# My_STM32_BOARD_MCU_SCH.net
KiCad netlist of a schematic drawn in Altium Designer
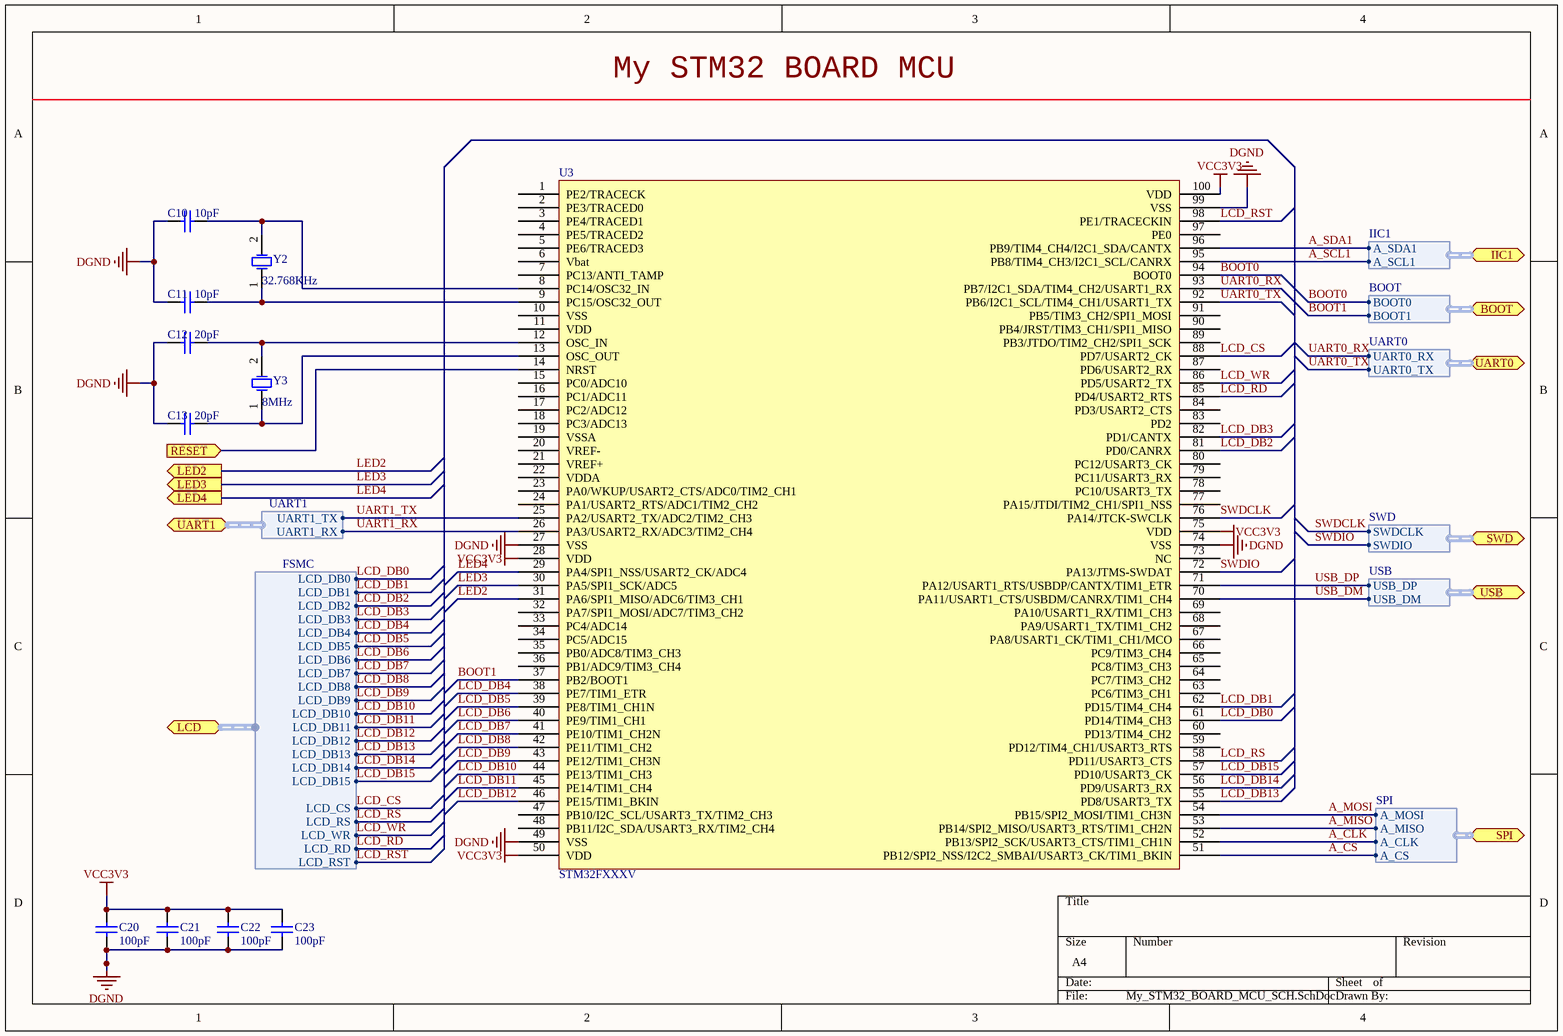
[diagram p0: My_STM32_BOARD_MCU_SCH.SchDoc]

(export (version "E")
  (design (tool "Eeschema 10.0.6"))
  (components
    (comp (ref "C10")
      (value "10pF")
      (footprint "0402")
      (description "Capacitor (Semiconductor SIM Model)")
      (fields (field (name "Comment") "Cap Semi") (field (name "PUBLISHER") "Altium Limited"))
      (libsource (lib "Miscellaneous Devices") (part "Cap Semi"))
    )
    (comp (ref "C11")
      (value "10pF")
      (footprint "0402")
      (description "Capacitor (Semiconductor SIM Model)")
      (fields (field (name "Comment") "Cap Semi") (field (name "PUBLISHER") "Altium Limited"))
      (libsource (lib "Miscellaneous Devices") (part "Cap Semi"))
    )
    (comp (ref "C12")
      (value "20pF")
      (footprint "0402")
      (description "Capacitor (Semiconductor SIM Model)")
      (fields (field (name "Comment") "Cap Semi") (field (name "PUBLISHER") "Altium Limited"))
      (libsource (lib "Miscellaneous Devices") (part "Cap Semi"))
    )
    (comp (ref "C13")
      (value "20pF")
      (footprint "0402")
      (description "Capacitor (Semiconductor SIM Model)")
      (fields (field (name "Comment") "Cap Semi") (field (name "PUBLISHER") "Altium Limited"))
      (libsource (lib "Miscellaneous Devices") (part "Cap Semi"))
    )
    (comp (ref "C20")
      (value "100pF")
      (footprint "0402")
      (description "Capacitor")
      (fields (field (name "Comment") "Cap") (field (name "PUBLISHER") "Altium Limited"))
      (libsource (lib "Miscellaneous Devices") (part "Cap"))
    )
    (comp (ref "C21")
      (value "100pF")
      (footprint "0402")
      (description "Capacitor")
      (fields (field (name "Comment") "Cap") (field (name "PUBLISHER") "Altium Limited"))
      (libsource (lib "Miscellaneous Devices") (part "Cap"))
    )
    (comp (ref "C22")
      (value "100pF")
      (footprint "0402")
      (description "Capacitor")
      (fields (field (name "Comment") "Cap") (field (name "PUBLISHER") "Altium Limited"))
      (libsource (lib "Miscellaneous Devices") (part "Cap"))
    )
    (comp (ref "C23")
      (value "100pF")
      (footprint "0402")
      (description "Capacitor")
      (fields (field (name "Comment") "Cap") (field (name "PUBLISHER") "Altium Limited"))
      (libsource (lib "Miscellaneous Devices") (part "Cap"))
    )
    (comp (ref "U3")
      (value "STM32FXXXV")
      (footprint "LQFP-100")
      (libsource (lib "My_Integrated_Library") (part "STM32FXXXV"))
    )
    (comp (ref "Y2")
      (value "32.768KHz")
      (footprint "XT_XTAL_32K")
      (description "XTAL")
      (libsource (lib "My_Integrated_Library") (part "XTAL"))
    )
    (comp (ref "Y3")
      (value "8MHz")
      (footprint "XT_HC49S_D")
      (description "XTAL")
      (libsource (lib "My_Integrated_Library") (part "XTAL"))
    )
  )
  (nets
    (net (code "9") (name "/A_CLK") (class "Default")
      (node (ref "U3") (pin "52") (pinfunction "PB13/SPI2_SCK/USART3_CTS/TIM1_CH1N_52") (pintype "passive"))
    )
    (net (code "10") (name "/A_CS") (class "Default")
      (node (ref "U3") (pin "51") (pinfunction "PB12/SPI2_NSS/I2C2_SMBAI/USART3_CK/TIM1_BKIN_51") (pintype "passive"))
    )
    (net (code "11") (name "/A_MISO") (class "Default")
      (node (ref "U3") (pin "53") (pinfunction "PB14/SPI2_MISO/USART3_RTS/TIM1_CH2N_53") (pintype "passive"))
    )
    (net (code "12") (name "/A_MOSI") (class "Default")
      (node (ref "U3") (pin "54") (pinfunction "PB15/SPI2_MOSI/TIM1_CH3N_54") (pintype "passive"))
    )
    (net (code "13") (name "/A_SCL1") (class "Default")
      (node (ref "U3") (pin "95") (pinfunction "PB8/TIM4_CH3/I2C1_SCL/CANRX_95") (pintype "passive"))
    )
    (net (code "14") (name "/A_SDA1") (class "Default")
      (node (ref "U3") (pin "96") (pinfunction "PB9/TIM4_CH4/I2C1_SDA/CANTX_96") (pintype "passive"))
    )
    (net (code "15") (name "/BOOT0") (class "Default")
      (node (ref "U3") (pin "94") (pinfunction "BOOT0_94") (pintype "passive"))
    )
    (net (code "16") (name "/BOOT1") (class "Default")
      (node (ref "U3") (pin "37") (pinfunction "PB2/BOOT1_37") (pintype "passive"))
    )
    (net (code "17") (name "/LCD_CS") (class "Default")
      (node (ref "U3") (pin "88") (pinfunction "PD7/USART2_CK_88") (pintype "passive"))
    )
    (net (code "18") (name "/LCD_DB0") (class "Default")
      (node (ref "U3") (pin "61") (pinfunction "PD14/TIM4_CH3_61") (pintype "passive"))
    )
    (net (code "19") (name "/LCD_DB1") (class "Default")
      (node (ref "U3") (pin "62") (pinfunction "PD15/TIM4_CH4_62") (pintype "passive"))
    )
    (net (code "20") (name "/LCD_DB2") (class "Default")
      (node (ref "U3") (pin "81") (pinfunction "PD0/CANRX_81") (pintype "passive"))
    )
    (net (code "21") (name "/LCD_DB3") (class "Default")
      (node (ref "U3") (pin "82") (pinfunction "PD1/CANTX_82") (pintype "passive"))
    )
    (net (code "22") (name "/LCD_DB4") (class "Default")
      (node (ref "U3") (pin "38") (pinfunction "PE7/TIM1_ETR_38") (pintype "passive"))
    )
    (net (code "23") (name "/LCD_DB5") (class "Default")
      (node (ref "U3") (pin "39") (pinfunction "PE8/TIM1_CH1N_39") (pintype "passive"))
    )
    (net (code "24") (name "/LCD_DB6") (class "Default")
      (node (ref "U3") (pin "40") (pinfunction "PE9/TIM1_CH1_40") (pintype "passive"))
    )
    (net (code "25") (name "/LCD_DB7") (class "Default")
      (node (ref "U3") (pin "41") (pinfunction "PE10/TIM1_CH2N_41") (pintype "passive"))
    )
    (net (code "26") (name "/LCD_DB8") (class "Default")
      (node (ref "U3") (pin "42") (pinfunction "PE11/TIM1_CH2_42") (pintype "passive"))
    )
    (net (code "27") (name "/LCD_DB9") (class "Default")
      (node (ref "U3") (pin "43") (pinfunction "PE12/TIM1_CH3N_43") (pintype "passive"))
    )
    (net (code "28") (name "/LCD_DB10") (class "Default")
      (node (ref "U3") (pin "44") (pinfunction "PE13/TIM1_CH3_44") (pintype "passive"))
    )
    (net (code "29") (name "/LCD_DB11") (class "Default")
      (node (ref "U3") (pin "45") (pinfunction "PE14/TIM1_CH4_45") (pintype "passive"))
    )
    (net (code "30") (name "/LCD_DB12") (class "Default")
      (node (ref "U3") (pin "46") (pinfunction "PE15/TIM1_BKIN_46") (pintype "passive"))
    )
    (net (code "31") (name "/LCD_DB13") (class "Default")
      (node (ref "U3") (pin "55") (pinfunction "PD8/USART3_TX_55") (pintype "passive"))
    )
    (net (code "32") (name "/LCD_DB14") (class "Default")
      (node (ref "U3") (pin "56") (pinfunction "PD9/USART3_RX_56") (pintype "passive"))
    )
    (net (code "33") (name "/LCD_DB15") (class "Default")
      (node (ref "U3") (pin "57") (pinfunction "PD10/USART3_CK_57") (pintype "passive"))
    )
    (net (code "34") (name "/LCD_RD") (class "Default")
      (node (ref "U3") (pin "85") (pinfunction "PD4/USART2_RTS_85") (pintype "passive"))
    )
    (net (code "35") (name "/LCD_RS") (class "Default")
      (node (ref "U3") (pin "58") (pinfunction "PD11/USART3_CTS_58") (pintype "passive"))
    )
    (net (code "36") (name "/LCD_RST") (class "Default")
      (node (ref "U3") (pin "98") (pinfunction "PE1/TRACECKIN_98") (pintype "passive"))
    )
    (net (code "37") (name "/LCD_WR") (class "Default")
      (node (ref "U3") (pin "86") (pinfunction "PD5/USART2_TX_86") (pintype "passive"))
    )
    (net (code "38") (name "/LED2") (class "Default")
      (node (ref "U3") (pin "31") (pinfunction "PA6/SPI1_MISO/ADC6/TIM3_CH1_31") (pintype "passive"))
    )
    (net (code "39") (name "/LED3") (class "Default")
      (node (ref "U3") (pin "30") (pinfunction "PA5/SPI1_SCK/ADC5_30") (pintype "passive"))
    )
    (net (code "40") (name "/LED4") (class "Default")
      (node (ref "U3") (pin "29") (pinfunction "PA4/SPI1_NSS/USART2_CK/ADC4_29") (pintype "passive"))
    )
    (net (code "41") (name "/RESET") (class "Default")
      (node (ref "U3") (pin "14") (pinfunction "NRST_14") (pintype "passive"))
    )
    (net (code "42") (name "/SWDCLK") (class "Default")
      (node (ref "U3") (pin "76") (pinfunction "PA14/JTCK-SWCLK_76") (pintype "passive"))
    )
    (net (code "43") (name "/SWDIO") (class "Default")
      (node (ref "U3") (pin "72") (pinfunction "PA13/JTMS-SWDAT_72") (pintype "passive"))
    )
    (net (code "44") (name "/UART0_RX") (class "Default")
      (node (ref "U3") (pin "93") (pinfunction "PB7/I2C1_SDA/TIM4_CH2/USART1_RX_93") (pintype "passive"))
    )
    (net (code "45") (name "/UART0_TX") (class "Default")
      (node (ref "U3") (pin "92") (pinfunction "PB6/I2C1_SCL/TIM4_CH1/USART1_TX_92") (pintype "passive"))
    )
    (net (code "46") (name "/UART1_RX") (class "Default")
      (node (ref "U3") (pin "26") (pinfunction "PA3/USART2_RX/ADC3/TIM2_CH4_26") (pintype "passive"))
    )
    (net (code "47") (name "/UART1_TX") (class "Default")
      (node (ref "U3") (pin "25") (pinfunction "PA2/USART2_TX/ADC2/TIM2_CH3_25") (pintype "passive"))
    )
    (net (code "48") (name "/USB_DM") (class "Default")
      (node (ref "U3") (pin "70") (pinfunction "PA11/USART1_CTS/USBDM/CANRX/TIM1_CH4_70") (pintype "passive"))
    )
    (net (code "49") (name "/USB_DP") (class "Default")
      (node (ref "U3") (pin "71") (pinfunction "PA12/USART1_RTS/USBDP/CANTX/TIM1_ETR_71") (pintype "passive"))
    )
    (net (code "58") (name "DGND") (class "Default")
      (node (ref "C10") (pin "1") (pinfunction "1_1") (pintype "passive"))
      (node (ref "C11") (pin "1") (pinfunction "1_1") (pintype "passive"))
      (node (ref "C12") (pin "1") (pinfunction "1_1") (pintype "passive"))
      (node (ref "C13") (pin "1") (pinfunction "1_1") (pintype "passive"))
      (node (ref "C20") (pin "1") (pinfunction "1_1") (pintype "passive"))
      (node (ref "C21") (pin "1") (pinfunction "1_1") (pintype "passive"))
      (node (ref "C22") (pin "1") (pinfunction "1_1") (pintype "passive"))
      (node (ref "C23") (pin "1") (pinfunction "1_1") (pintype "passive"))
      (node (ref "U3") (pin "27") (pinfunction "VSS_27") (pintype "passive"))
      (node (ref "U3") (pin "49") (pinfunction "VSS_49") (pintype "passive"))
      (node (ref "U3") (pin "74") (pinfunction "VSS_74") (pintype "passive"))
      (node (ref "U3") (pin "99") (pinfunction "VSS_99") (pintype "passive"))
    )
    (net (code "59") (name "Net-(U3-OSC_IN)") (class "Default")
      (node (ref "C12") (pin "2") (pinfunction "2_2") (pintype "passive"))
      (node (ref "U3") (pin "12") (pinfunction "OSC_IN_12") (pintype "passive"))
      (node (ref "Y3") (pin "2") (pinfunction "2_2") (pintype "passive"))
    )
    (net (code "60") (name "Net-(U3-OSC_OUT)") (class "Default")
      (node (ref "C13") (pin "2") (pinfunction "2_2") (pintype "passive"))
      (node (ref "U3") (pin "13") (pinfunction "OSC_OUT_13") (pintype "passive"))
      (node (ref "Y3") (pin "1") (pinfunction "1_1") (pintype "passive"))
    )
    (net (code "61") (name "Net-(U3-PC14{slash}OSC32_IN)") (class "Default")
      (node (ref "C10") (pin "2") (pinfunction "2_2") (pintype "passive"))
      (node (ref "U3") (pin "8") (pinfunction "PC14/OSC32_IN_8") (pintype "passive"))
      (node (ref "Y2") (pin "2") (pinfunction "2_2") (pintype "passive"))
    )
    (net (code "62") (name "Net-(U3-PC15{slash}OSC32_OUT)") (class "Default")
      (node (ref "C11") (pin "2") (pinfunction "2_2") (pintype "passive"))
      (node (ref "U3") (pin "9") (pinfunction "PC15/OSC32_OUT_9") (pintype "passive"))
      (node (ref "Y2") (pin "1") (pinfunction "1_1") (pintype "passive"))
    )
    (net (code "63") (name "VCC3V3") (class "Default")
      (node (ref "C20") (pin "2") (pinfunction "2_2") (pintype "passive"))
      (node (ref "C21") (pin "2") (pinfunction "2_2") (pintype "passive"))
      (node (ref "C22") (pin "2") (pinfunction "2_2") (pintype "passive"))
      (node (ref "C23") (pin "2") (pinfunction "2_2") (pintype "passive"))
      (node (ref "U3") (pin "100") (pinfunction "VDD_100") (pintype "passive"))
      (node (ref "U3") (pin "28") (pinfunction "VDD_28") (pintype "passive"))
      (node (ref "U3") (pin "50") (pinfunction "VDD_50") (pintype "passive"))
      (node (ref "U3") (pin "75") (pinfunction "VDD_75") (pintype "passive"))
    )
    (net (code "64") (name "unconnected-(U3-NC-Pad73)") (class "Default")
      (node (ref "U3") (pin "73") (pinfunction "NC_73") (pintype "passive"))
    )
    (net (code "65") (name "unconnected-(U3-PA0{slash}WKUP{slash}USART2_CTS{slash}ADC0{slash}TIM2_CH1-Pad23)") (class "Default")
      (node (ref "U3") (pin "23") (pinfunction "PA0/WKUP/USART2_CTS/ADC0/TIM2_CH1_23") (pintype "passive"))
    )
    (net (code "66") (name "unconnected-(U3-PA1{slash}USART2_RTS{slash}ADC1{slash}TIM2_CH2-Pad24)") (class "Default")
      (node (ref "U3") (pin "24") (pinfunction "PA1/USART2_RTS/ADC1/TIM2_CH2_24") (pintype "passive"))
    )
    (net (code "67") (name "unconnected-(U3-PA7{slash}SPI1_MOSI{slash}ADC7{slash}TIM3_CH2-Pad32)") (class "Default")
      (node (ref "U3") (pin "32") (pinfunction "PA7/SPI1_MOSI/ADC7/TIM3_CH2_32") (pintype "passive"))
    )
    (net (code "68") (name "unconnected-(U3-PA8{slash}USART1_CK{slash}TIM1_CH1{slash}MCO-Pad67)") (class "Default")
      (node (ref "U3") (pin "67") (pinfunction "PA8/USART1_CK/TIM1_CH1/MCO_67") (pintype "passive"))
    )
    (net (code "69") (name "unconnected-(U3-PA9{slash}USART1_TX{slash}TIM1_CH2-Pad68)") (class "Default")
      (node (ref "U3") (pin "68") (pinfunction "PA9/USART1_TX/TIM1_CH2_68") (pintype "passive"))
    )
    (net (code "70") (name "unconnected-(U3-PA10{slash}USART1_RX{slash}TIM1_CH3-Pad69)") (class "Default")
      (node (ref "U3") (pin "69") (pinfunction "PA10/USART1_RX/TIM1_CH3_69") (pintype "passive"))
    )
    (net (code "71") (name "unconnected-(U3-PA15{slash}JTDI{slash}TIM2_CH1{slash}SPI1_NSS-Pad77)") (class "Default")
      (node (ref "U3") (pin "77") (pinfunction "PA15/JTDI/TIM2_CH1/SPI1_NSS_77") (pintype "passive"))
    )
    (net (code "72") (name "unconnected-(U3-PB0{slash}ADC8{slash}TIM3_CH3-Pad35)") (class "Default")
      (node (ref "U3") (pin "35") (pinfunction "PB0/ADC8/TIM3_CH3_35") (pintype "passive"))
    )
    (net (code "73") (name "unconnected-(U3-PB1{slash}ADC9{slash}TIM3_CH4-Pad36)") (class "Default")
      (node (ref "U3") (pin "36") (pinfunction "PB1/ADC9/TIM3_CH4_36") (pintype "passive"))
    )
    (net (code "74") (name "unconnected-(U3-PB3{slash}JTDO{slash}TIM2_CH2{slash}SPI1_SCK-Pad89)") (class "Default")
      (node (ref "U3") (pin "89") (pinfunction "PB3/JTDO/TIM2_CH2/SPI1_SCK_89") (pintype "passive"))
    )
    (net (code "75") (name "unconnected-(U3-PB4{slash}JRST{slash}TIM3_CH1{slash}SPI1_MISO-Pad90)") (class "Default")
      (node (ref "U3") (pin "90") (pinfunction "PB4/JRST/TIM3_CH1/SPI1_MISO_90") (pintype "passive"))
    )
    (net (code "76") (name "unconnected-(U3-PB5{slash}TIM3_CH2{slash}SPI1_MOSI-Pad91)") (class "Default")
      (node (ref "U3") (pin "91") (pinfunction "PB5/TIM3_CH2/SPI1_MOSI_91") (pintype "passive"))
    )
    (net (code "77") (name "unconnected-(U3-PB10{slash}I2C_SCL{slash}USART3_TX{slash}TIM2_CH3-Pad47)") (class "Default")
      (node (ref "U3") (pin "47") (pinfunction "PB10/I2C_SCL/USART3_TX/TIM2_CH3_47") (pintype "passive"))
    )
    (net (code "78") (name "unconnected-(U3-PB11{slash}I2C_SDA{slash}USART3_RX{slash}TIM2_CH4-Pad48)") (class "Default")
      (node (ref "U3") (pin "48") (pinfunction "PB11/I2C_SDA/USART3_RX/TIM2_CH4_48") (pintype "passive"))
    )
    (net (code "79") (name "unconnected-(U3-PC0{slash}ADC10-Pad15)") (class "Default")
      (node (ref "U3") (pin "15") (pinfunction "PC0/ADC10_15") (pintype "passive"))
    )
    (net (code "80") (name "unconnected-(U3-PC1{slash}ADC11-Pad16)") (class "Default")
      (node (ref "U3") (pin "16") (pinfunction "PC1/ADC11_16") (pintype "passive"))
    )
    (net (code "81") (name "unconnected-(U3-PC2{slash}ADC12-Pad17)") (class "Default")
      (node (ref "U3") (pin "17") (pinfunction "PC2/ADC12_17") (pintype "passive"))
    )
    (net (code "82") (name "unconnected-(U3-PC3{slash}ADC13-Pad18)") (class "Default")
      (node (ref "U3") (pin "18") (pinfunction "PC3/ADC13_18") (pintype "passive"))
    )
    (net (code "83") (name "unconnected-(U3-PC4{slash}ADC14-Pad33)") (class "Default")
      (node (ref "U3") (pin "33") (pinfunction "PC4/ADC14_33") (pintype "passive"))
    )
    (net (code "84") (name "unconnected-(U3-PC5{slash}ADC15-Pad34)") (class "Default")
      (node (ref "U3") (pin "34") (pinfunction "PC5/ADC15_34") (pintype "passive"))
    )
    (net (code "85") (name "unconnected-(U3-PC6{slash}TIM3_CH1-Pad63)") (class "Default")
      (node (ref "U3") (pin "63") (pinfunction "PC6/TIM3_CH1_63") (pintype "passive"))
    )
    (net (code "86") (name "unconnected-(U3-PC7{slash}TIM3_CH2-Pad64)") (class "Default")
      (node (ref "U3") (pin "64") (pinfunction "PC7/TIM3_CH2_64") (pintype "passive"))
    )
    (net (code "87") (name "unconnected-(U3-PC8{slash}TIM3_CH3-Pad65)") (class "Default")
      (node (ref "U3") (pin "65") (pinfunction "PC8/TIM3_CH3_65") (pintype "passive"))
    )
    (net (code "88") (name "unconnected-(U3-PC9{slash}TIM3_CH4-Pad66)") (class "Default")
      (node (ref "U3") (pin "66") (pinfunction "PC9/TIM3_CH4_66") (pintype "passive"))
    )
    (net (code "89") (name "unconnected-(U3-PC10{slash}USART3_TX-Pad78)") (class "Default")
      (node (ref "U3") (pin "78") (pinfunction "PC10/USART3_TX_78") (pintype "passive"))
    )
    (net (code "90") (name "unconnected-(U3-PC11{slash}USART3_RX-Pad79)") (class "Default")
      (node (ref "U3") (pin "79") (pinfunction "PC11/USART3_RX_79") (pintype "passive"))
    )
    (net (code "91") (name "unconnected-(U3-PC12{slash}USART3_CK-Pad80)") (class "Default")
      (node (ref "U3") (pin "80") (pinfunction "PC12/USART3_CK_80") (pintype "passive"))
    )
    (net (code "92") (name "unconnected-(U3-PC13{slash}ANTI_TAMP-Pad7)") (class "Default")
      (node (ref "U3") (pin "7") (pinfunction "PC13/ANTI_TAMP_7") (pintype "passive"))
    )
    (net (code "93") (name "unconnected-(U3-PD2-Pad83)") (class "Default")
      (node (ref "U3") (pin "83") (pinfunction "PD2_83") (pintype "passive"))
    )
    (net (code "94") (name "unconnected-(U3-PD3{slash}USART2_CTS-Pad84)") (class "Default")
      (node (ref "U3") (pin "84") (pinfunction "PD3/USART2_CTS_84") (pintype "passive"))
    )
    (net (code "95") (name "unconnected-(U3-PD6{slash}USART2_RX-Pad87)") (class "Default")
      (node (ref "U3") (pin "87") (pinfunction "PD6/USART2_RX_87") (pintype "passive"))
    )
    (net (code "96") (name "unconnected-(U3-PD12{slash}TIM4_CH1{slash}USART3_RTS-Pad59)") (class "Default")
      (node (ref "U3") (pin "59") (pinfunction "PD12/TIM4_CH1/USART3_RTS_59") (pintype "passive"))
    )
    (net (code "97") (name "unconnected-(U3-PD13{slash}TIM4_CH2-Pad60)") (class "Default")
      (node (ref "U3") (pin "60") (pinfunction "PD13/TIM4_CH2_60") (pintype "passive"))
    )
    (net (code "98") (name "unconnected-(U3-PE0-Pad97)") (class "Default")
      (node (ref "U3") (pin "97") (pinfunction "PE0_97") (pintype "passive"))
    )
    (net (code "99") (name "unconnected-(U3-PE2{slash}TRACECK-Pad1)") (class "Default")
      (node (ref "U3") (pin "1") (pinfunction "PE2/TRACECK_1") (pintype "passive"))
    )
    (net (code "100") (name "unconnected-(U3-PE3{slash}TRACED0-Pad2)") (class "Default")
      (node (ref "U3") (pin "2") (pinfunction "PE3/TRACED0_2") (pintype "passive"))
    )
    (net (code "101") (name "unconnected-(U3-PE4{slash}TRACED1-Pad3)") (class "Default")
      (node (ref "U3") (pin "3") (pinfunction "PE4/TRACED1_3") (pintype "passive"))
    )
    (net (code "102") (name "unconnected-(U3-PE5{slash}TRACED2-Pad4)") (class "Default")
      (node (ref "U3") (pin "4") (pinfunction "PE5/TRACED2_4") (pintype "passive"))
    )
    (net (code "103") (name "unconnected-(U3-PE6{slash}TRACED3-Pad5)") (class "Default")
      (node (ref "U3") (pin "5") (pinfunction "PE6/TRACED3_5") (pintype "passive"))
    )
    (net (code "104") (name "unconnected-(U3-VDD-Pad11)") (class "Default")
      (node (ref "U3") (pin "11") (pinfunction "VDD_11") (pintype "passive"))
    )
    (net (code "105") (name "unconnected-(U3-VDDA-Pad22)") (class "Default")
      (node (ref "U3") (pin "22") (pinfunction "VDDA_22") (pintype "passive"))
    )
    (net (code "106") (name "unconnected-(U3-VREF+-Pad21)") (class "Default")
      (node (ref "U3") (pin "21") (pinfunction "VREF+_21") (pintype "passive"))
    )
    (net (code "107") (name "unconnected-(U3-VREF--Pad20)") (class "Default")
      (node (ref "U3") (pin "20") (pinfunction "VREF-_20") (pintype "passive"))
    )
    (net (code "108") (name "unconnected-(U3-VSS-Pad10)") (class "Default")
      (node (ref "U3") (pin "10") (pinfunction "VSS_10") (pintype "passive"))
    )
    (net (code "109") (name "unconnected-(U3-VSSA-Pad19)") (class "Default")
      (node (ref "U3") (pin "19") (pinfunction "VSSA_19") (pintype "passive"))
    )
    (net (code "110") (name "unconnected-(U3-Vbat-Pad6)") (class "Default")
      (node (ref "U3") (pin "6") (pinfunction "Vbat_6") (pintype "passive"))
    )
  )
)
